# Overview.net
KiCad netlist of a schematic drawn in Altium Designer
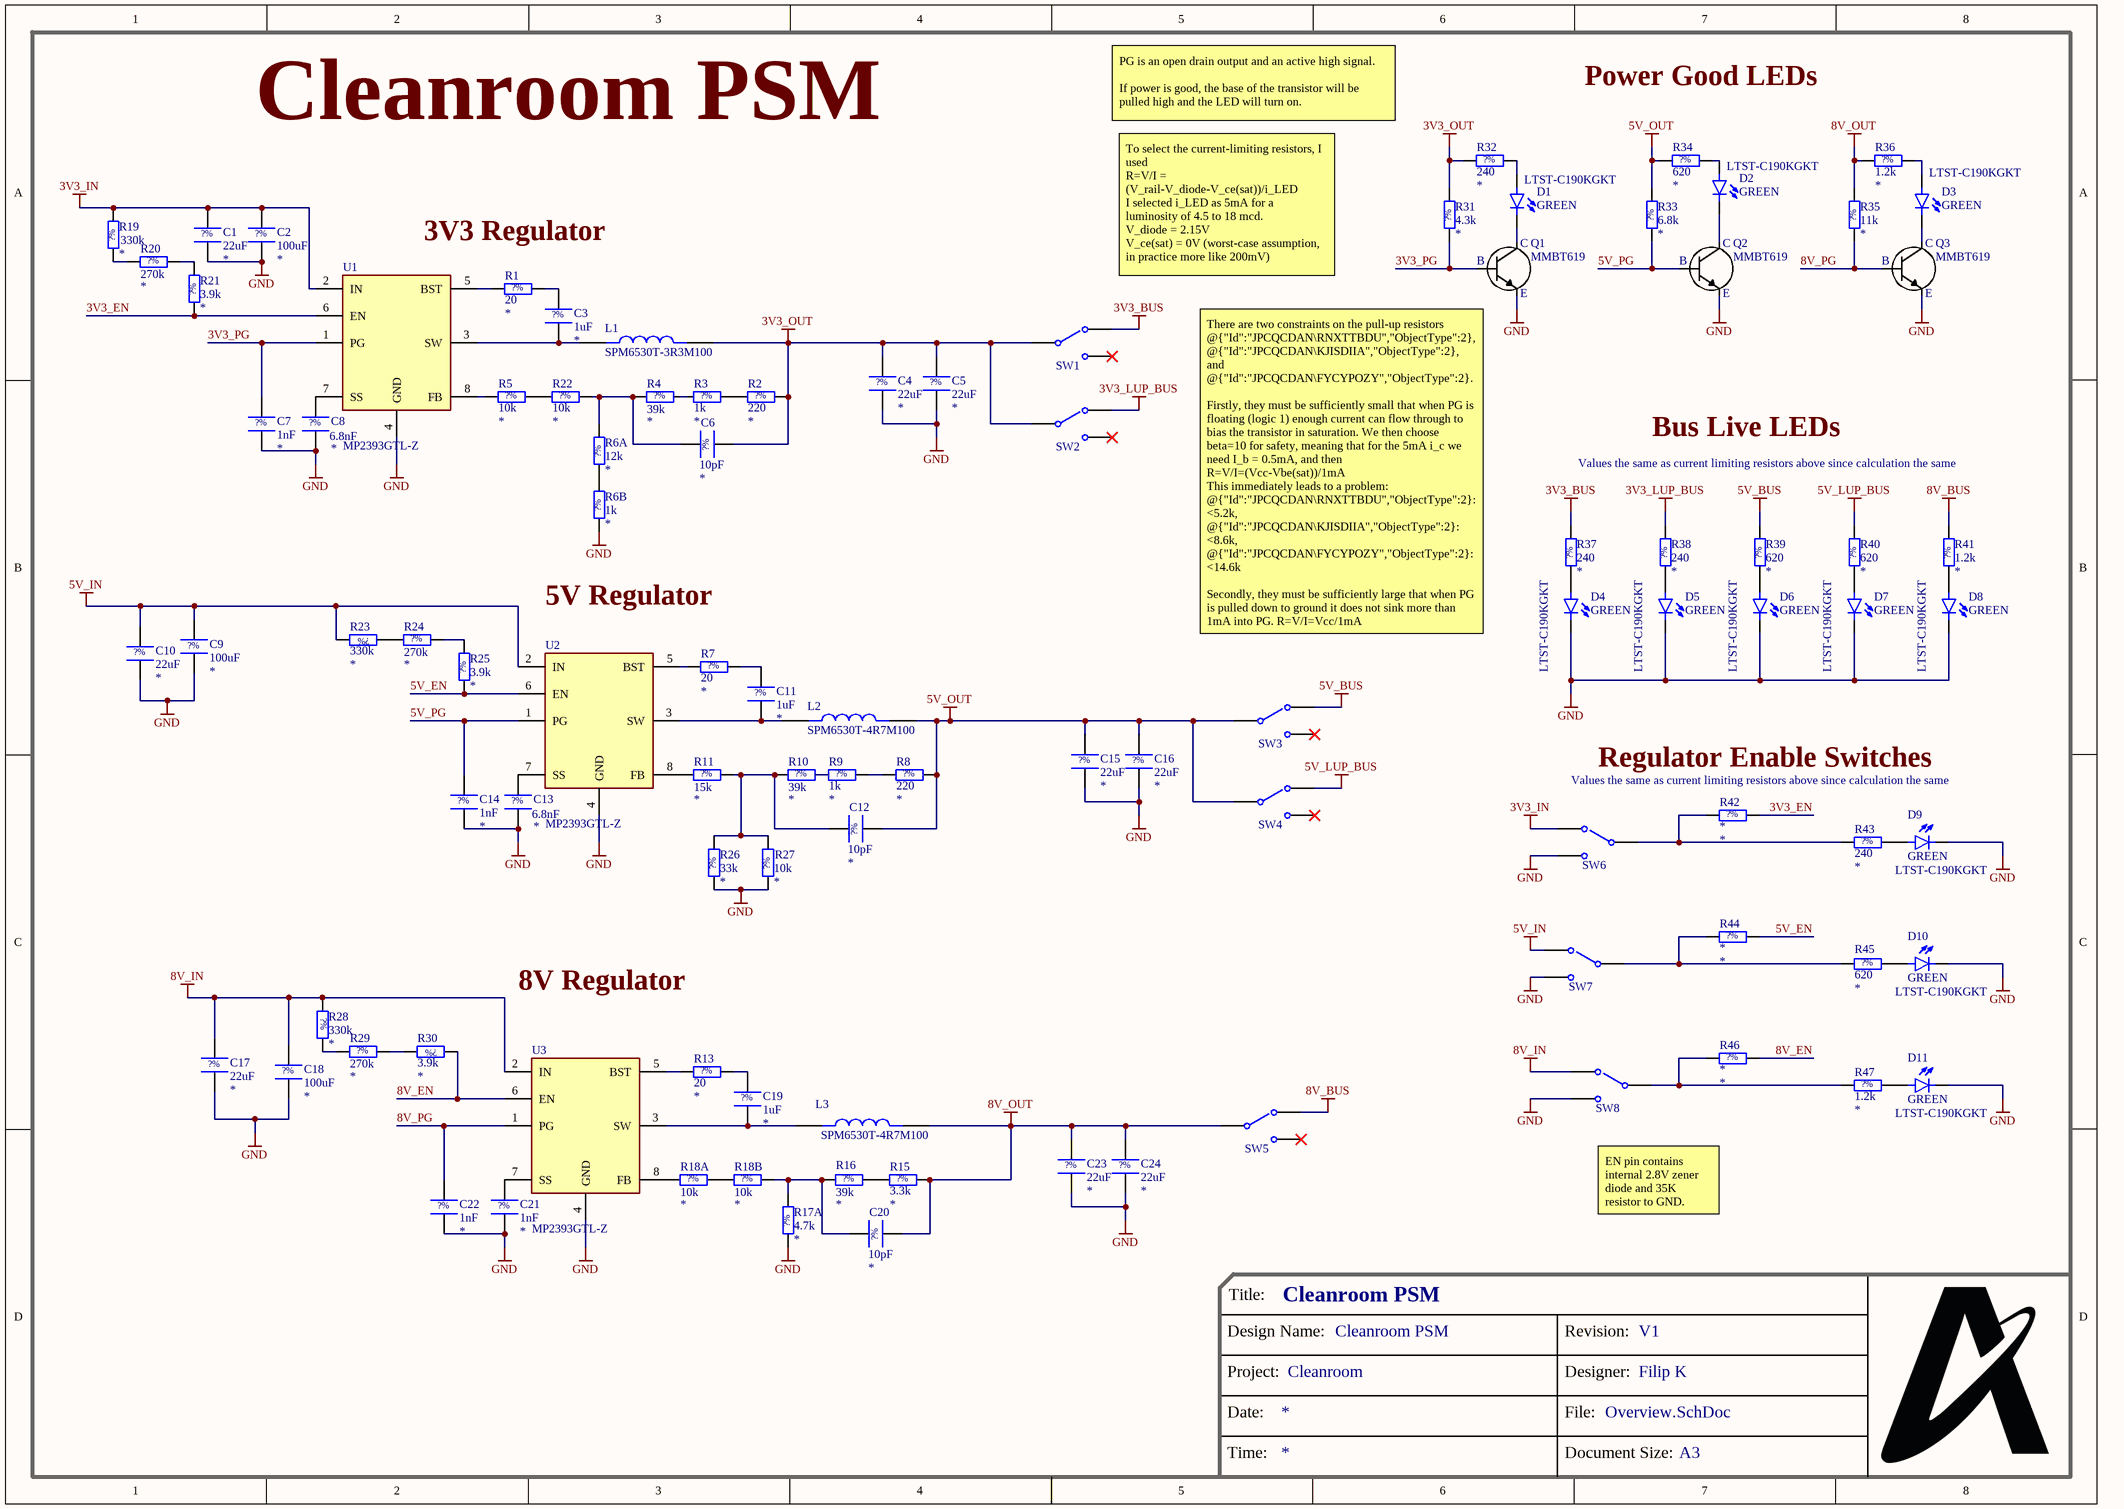
[diagram p0: Overview.SchDoc]

(export (version "E")
  (design (tool "Eeschema 10.0.6"))
  (components
    (comp (ref "C1")
      (value "22uF")
      (footprint "CAPACITOR_0805_2012M-70N")
      (description "Passive - Capacitor, Generic")
      (fields (field (name "TOLERANCE") "?%") (field (name "MF PART NO.") "*"))
      (libsource (lib "APSS Generic Components (3)") (part "Generic Capacitor"))
    )
    (comp (ref "C2")
      (value "100uF")
      (footprint "CAPACITOR_0805_2012M-70N")
      (description "Passive - Capacitor, Generic")
      (fields (field (name "TOLERANCE") "?%") (field (name "MF PART NO.") "*"))
      (libsource (lib "APSS Generic Components (3)") (part "Generic Capacitor"))
    )
    (comp (ref "C3")
      (value "1uF")
      (footprint "CAPACITOR_0805_2012M-70N")
      (description "Passive - Capacitor, Generic")
      (fields (field (name "TOLERANCE") "?%") (field (name "MF PART NO.") "*"))
      (libsource (lib "APSS Generic Components (3)") (part "Generic Capacitor"))
    )
    (comp (ref "C4")
      (value "22uF")
      (footprint "CAPACITOR_0805_2012M-70N")
      (description "Passive - Capacitor, Generic")
      (fields (field (name "TOLERANCE") "?%") (field (name "MF PART NO.") "*"))
      (libsource (lib "APSS Generic Components (3)") (part "Generic Capacitor"))
    )
    (comp (ref "C5")
      (value "22uF")
      (footprint "CAPACITOR_0805_2012M-70N")
      (description "Passive - Capacitor, Generic")
      (fields (field (name "TOLERANCE") "?%") (field (name "MF PART NO.") "*"))
      (libsource (lib "APSS Generic Components (3)") (part "Generic Capacitor"))
    )
    (comp (ref "C6")
      (value "10pF")
      (footprint "CAPACITOR_0805_2012M-70N")
      (description "Passive - Capacitor, Generic")
      (fields (field (name "TOLERANCE") "?%") (field (name "MF PART NO.") "*"))
      (libsource (lib "APSS Generic Components (3)") (part "Generic Capacitor"))
    )
    (comp (ref "C7")
      (value "1nF")
      (footprint "CAPACITOR_0805_2012M-70N")
      (description "Passive - Capacitor, Generic")
      (fields (field (name "TOLERANCE") "?%") (field (name "MF PART NO.") "*"))
      (libsource (lib "APSS Generic Components (3)") (part "Generic Capacitor"))
    )
    (comp (ref "C8")
      (value "6.8nF")
      (footprint "CAPACITOR_0805_2012M-70N")
      (description "Passive - Capacitor, Generic")
      (fields (field (name "TOLERANCE") "?%") (field (name "MF PART NO.") "*"))
      (libsource (lib "APSS Generic Components (3)") (part "Generic Capacitor"))
    )
    (comp (ref "C9")
      (value "100uF")
      (footprint "CAPACITOR_0805_2012M-70N")
      (description "Passive - Capacitor, Generic")
      (fields (field (name "TOLERANCE") "?%") (field (name "MF PART NO.") "*"))
      (libsource (lib "APSS Generic Components (3)") (part "Generic Capacitor"))
    )
    (comp (ref "C10")
      (value "22uF")
      (footprint "CAPACITOR_0805_2012M-70N")
      (description "Passive - Capacitor, Generic")
      (fields (field (name "TOLERANCE") "?%") (field (name "MF PART NO.") "*"))
      (libsource (lib "APSS Generic Components (3)") (part "Generic Capacitor"))
    )
    (comp (ref "C11")
      (value "1uF")
      (footprint "CAPACITOR_0805_2012M-70N")
      (description "Passive - Capacitor, Generic")
      (fields (field (name "TOLERANCE") "?%") (field (name "MF PART NO.") "*"))
      (libsource (lib "APSS Generic Components (3)") (part "Generic Capacitor"))
    )
    (comp (ref "C12")
      (value "10pF")
      (footprint "CAPACITOR_0805_2012M-70N")
      (description "Passive - Capacitor, Generic")
      (fields (field (name "TOLERANCE") "?%") (field (name "MF PART NO.") "*"))
      (libsource (lib "APSS Generic Components (3)") (part "Generic Capacitor"))
    )
    (comp (ref "C13")
      (value "6.8nF")
      (footprint "CAPACITOR_0805_2012M-70N")
      (description "Passive - Capacitor, Generic")
      (fields (field (name "TOLERANCE") "?%") (field (name "MF PART NO.") "*"))
      (libsource (lib "APSS Generic Components (3)") (part "Generic Capacitor"))
    )
    (comp (ref "C14")
      (value "1nF")
      (footprint "CAPACITOR_0805_2012M-70N")
      (description "Passive - Capacitor, Generic")
      (fields (field (name "TOLERANCE") "?%") (field (name "MF PART NO.") "*"))
      (libsource (lib "APSS Generic Components (3)") (part "Generic Capacitor"))
    )
    (comp (ref "C15")
      (value "22uF")
      (footprint "CAPACITOR_0805_2012M-70N")
      (description "Passive - Capacitor, Generic")
      (fields (field (name "TOLERANCE") "?%") (field (name "MF PART NO.") "*"))
      (libsource (lib "APSS Generic Components (3)") (part "Generic Capacitor"))
    )
    (comp (ref "C16")
      (value "22uF")
      (footprint "CAPACITOR_0805_2012M-70N")
      (description "Passive - Capacitor, Generic")
      (fields (field (name "TOLERANCE") "?%") (field (name "MF PART NO.") "*"))
      (libsource (lib "APSS Generic Components (3)") (part "Generic Capacitor"))
    )
    (comp (ref "C17")
      (value "22uF")
      (footprint "CAPACITOR_0805_2012M-70N")
      (description "Passive - Capacitor, Generic")
      (fields (field (name "TOLERANCE") "?%") (field (name "MF PART NO.") "*"))
      (libsource (lib "APSS Generic Components (3)") (part "Generic Capacitor"))
    )
    (comp (ref "C18")
      (value "100uF")
      (footprint "CAPACITOR_0805_2012M-70N")
      (description "Passive - Capacitor, Generic")
      (fields (field (name "TOLERANCE") "?%") (field (name "MF PART NO.") "*"))
      (libsource (lib "APSS Generic Components (3)") (part "Generic Capacitor"))
    )
    (comp (ref "C19")
      (value "1uF")
      (footprint "CAPACITOR_0805_2012M-70N")
      (description "Passive - Capacitor, Generic")
      (fields (field (name "TOLERANCE") "?%") (field (name "MF PART NO.") "*"))
      (libsource (lib "APSS Generic Components (3)") (part "Generic Capacitor"))
    )
    (comp (ref "C20")
      (value "10pF")
      (footprint "CAPACITOR_0805_2012M-70N")
      (description "Passive - Capacitor, Generic")
      (fields (field (name "TOLERANCE") "?%") (field (name "MF PART NO.") "*"))
      (libsource (lib "APSS Generic Components (3)") (part "Generic Capacitor"))
    )
    (comp (ref "C21")
      (value "1nF")
      (footprint "CAPACITOR_0805_2012M-70N")
      (description "Passive - Capacitor, Generic")
      (fields (field (name "TOLERANCE") "?%") (field (name "MF PART NO.") "*"))
      (libsource (lib "APSS Generic Components (3)") (part "Generic Capacitor"))
    )
    (comp (ref "C22")
      (value "1nF")
      (footprint "CAPACITOR_0805_2012M-70N")
      (description "Passive - Capacitor, Generic")
      (fields (field (name "TOLERANCE") "?%") (field (name "MF PART NO.") "*"))
      (libsource (lib "APSS Generic Components (3)") (part "Generic Capacitor"))
    )
    (comp (ref "C23")
      (value "22uF")
      (footprint "CAPACITOR_0805_2012M-70N")
      (description "Passive - Capacitor, Generic")
      (fields (field (name "TOLERANCE") "?%") (field (name "MF PART NO.") "*"))
      (libsource (lib "APSS Generic Components (3)") (part "Generic Capacitor"))
    )
    (comp (ref "C24")
      (value "22uF")
      (footprint "CAPACITOR_0805_2012M-70N")
      (description "Passive - Capacitor, Generic")
      (fields (field (name "TOLERANCE") "?%") (field (name "MF PART NO.") "*"))
      (libsource (lib "APSS Generic Components (3)") (part "Generic Capacitor"))
    )
    (comp (ref "D1")
      (value "LTST-C190 Series")
      (footprint "APSS Prototype Parts:LED_0603_1608M_0.80mm")
      (description "Diode - LED, 0603")
      (fields
        (field (name "APSS STANDARD PART") "APSS Standard")
        (field (name "MF PART NO.") "LTST-C190KGKT")
        (field (name "COLOUR") "GREEN")
      )
      (libsource (lib "APSS Prototype Parts") (part "LTST-C190 Series"))
    )
    (comp (ref "D2")
      (value "LTST-C190 Series")
      (footprint "APSS Prototype Parts:LED_0603_1608M_0.80mm")
      (description "Diode - LED, 0603")
      (fields
        (field (name "APSS STANDARD PART") "APSS Standard")
        (field (name "MF PART NO.") "LTST-C190KGKT")
        (field (name "COLOUR") "GREEN")
      )
      (libsource (lib "APSS Prototype Parts") (part "LTST-C190 Series"))
    )
    (comp (ref "D3")
      (value "LTST-C190 Series")
      (footprint "APSS Prototype Parts:LED_0603_1608M_0.80mm")
      (description "Diode - LED, 0603")
      (fields
        (field (name "APSS STANDARD PART") "APSS Standard")
        (field (name "MF PART NO.") "LTST-C190KGKT")
        (field (name "COLOUR") "GREEN")
      )
      (libsource (lib "APSS Prototype Parts") (part "LTST-C190 Series"))
    )
    (comp (ref "D4")
      (value "LTST-C190 Series")
      (footprint "APSS Prototype Parts:LED_0603_1608M_0.80mm")
      (description "Diode - LED, 0603")
      (fields
        (field (name "APSS STANDARD PART") "APSS Standard")
        (field (name "MF PART NO.") "LTST-C190KGKT")
        (field (name "COLOUR") "GREEN")
      )
      (libsource (lib "APSS Prototype Parts") (part "LTST-C190 Series"))
    )
    (comp (ref "D5")
      (value "LTST-C190 Series")
      (footprint "APSS Prototype Parts:LED_0603_1608M_0.80mm")
      (description "Diode - LED, 0603")
      (fields
        (field (name "APSS STANDARD PART") "APSS Standard")
        (field (name "MF PART NO.") "LTST-C190KGKT")
        (field (name "COLOUR") "GREEN")
      )
      (libsource (lib "APSS Prototype Parts") (part "LTST-C190 Series"))
    )
    (comp (ref "D6")
      (value "LTST-C190 Series")
      (footprint "APSS Prototype Parts:LED_0603_1608M_0.80mm")
      (description "Diode - LED, 0603")
      (fields
        (field (name "APSS STANDARD PART") "APSS Standard")
        (field (name "MF PART NO.") "LTST-C190KGKT")
        (field (name "COLOUR") "GREEN")
      )
      (libsource (lib "APSS Prototype Parts") (part "LTST-C190 Series"))
    )
    (comp (ref "D7")
      (value "LTST-C190 Series")
      (footprint "APSS Prototype Parts:LED_0603_1608M_0.80mm")
      (description "Diode - LED, 0603")
      (fields
        (field (name "APSS STANDARD PART") "APSS Standard")
        (field (name "MF PART NO.") "LTST-C190KGKT")
        (field (name "COLOUR") "GREEN")
      )
      (libsource (lib "APSS Prototype Parts") (part "LTST-C190 Series"))
    )
    (comp (ref "D8")
      (value "LTST-C190 Series")
      (footprint "APSS Prototype Parts:LED_0603_1608M_0.80mm")
      (description "Diode - LED, 0603")
      (fields
        (field (name "APSS STANDARD PART") "APSS Standard")
        (field (name "MF PART NO.") "LTST-C190KGKT")
        (field (name "COLOUR") "GREEN")
      )
      (libsource (lib "APSS Prototype Parts") (part "LTST-C190 Series"))
    )
    (comp (ref "D9")
      (value "LTST-C190 Series")
      (footprint "APSS Prototype Parts:LED_0603_1608M_0.80mm")
      (description "Diode - LED, 0603")
      (fields
        (field (name "APSS STANDARD PART") "APSS Standard")
        (field (name "MF PART NO.") "LTST-C190KGKT")
        (field (name "COLOUR") "GREEN")
      )
      (libsource (lib "APSS Prototype Parts") (part "LTST-C190 Series"))
    )
    (comp (ref "D10")
      (value "LTST-C190 Series")
      (footprint "APSS Prototype Parts:LED_0603_1608M_0.80mm")
      (description "Diode - LED, 0603")
      (fields
        (field (name "APSS STANDARD PART") "APSS Standard")
        (field (name "MF PART NO.") "LTST-C190KGKT")
        (field (name "COLOUR") "GREEN")
      )
      (libsource (lib "APSS Prototype Parts") (part "LTST-C190 Series"))
    )
    (comp (ref "D11")
      (value "LTST-C190 Series")
      (footprint "APSS Prototype Parts:LED_0603_1608M_0.80mm")
      (description "Diode - LED, 0603")
      (fields
        (field (name "APSS STANDARD PART") "APSS Standard")
        (field (name "MF PART NO.") "LTST-C190KGKT")
        (field (name "COLOUR") "GREEN")
      )
      (libsource (lib "APSS Prototype Parts") (part "LTST-C190 Series"))
    )
    (comp (ref "L1")
      (value "SPM6530T-3R3M100")
      (footprint "IND_SPM6530T-1R5M100")
      (description "1.5 ÂµH Shielded Drum Core, Wirewound Inductor 11 A 10.67mOhm Max Nonstandard")
      (fields (field (name "DIGI-KEY_PART_NUMBER") "445-3881-2-ND") (field (name "MF") "TDK"))
      (libsource (lib "SPM6530T-1R5M100") (part "SPM6530T-1R5M100"))
    )
    (comp (ref "L2")
      (value "SPM6530T-4R7M100")
      (footprint "IND_SPM6530T-1R5M100")
      (description "1.5 ÂµH Shielded Drum Core, Wirewound Inductor 11 A 10.67mOhm Max Nonstandard")
      (fields (field (name "DIGI-KEY_PART_NUMBER") "445-3881-2-ND") (field (name "MF") "TDK"))
      (libsource (lib "SPM6530T-1R5M100") (part "SPM6530T-1R5M100"))
    )
    (comp (ref "L3")
      (value "SPM6530T-4R7M100")
      (footprint "IND_SPM6530T-1R5M100")
      (description "1.5 ÂµH Shielded Drum Core, Wirewound Inductor 11 A 10.67mOhm Max Nonstandard")
      (fields (field (name "DIGI-KEY_PART_NUMBER") "445-3881-2-ND") (field (name "MF") "TDK"))
      (libsource (lib "SPM6530T-1R5M100") (part "SPM6530T-1R5M100"))
    )
    (comp (ref "Q1")
      (value "MMBT619")
      (footprint "APSS Prototype Parts:SOT23-3N-1.15mm")
      (description "Transistor - BJT NPN MMBT619")
      (fields (field (name "POWER") "350mW") (field (name "APSS STANDARD PART") "APSS Standard"))
      (libsource (lib "APSS Prototype Parts") (part "MMBT619"))
    )
    (comp (ref "Q2")
      (value "MMBT619")
      (footprint "APSS Prototype Parts:SOT23-3N-1.15mm")
      (description "Transistor - BJT NPN MMBT619")
      (fields (field (name "POWER") "350mW") (field (name "APSS STANDARD PART") "APSS Standard"))
      (libsource (lib "APSS Prototype Parts") (part "MMBT619"))
    )
    (comp (ref "Q3")
      (value "MMBT619")
      (footprint "APSS Prototype Parts:SOT23-3N-1.15mm")
      (description "Transistor - BJT NPN MMBT619")
      (fields (field (name "POWER") "350mW") (field (name "APSS STANDARD PART") "APSS Standard"))
      (libsource (lib "APSS Prototype Parts") (part "MMBT619"))
    )
    (comp (ref "R1")
      (value "20")
      (footprint "RESISTOR_0805_2012M-50N")
      (description "Passive - Resistor, Generic")
      (fields (field (name "TOLERANCE") "?%") (field (name "MF PART NO.") "*"))
      (libsource (lib "APSS Generic Components (3)") (part "Generic Resistor"))
    )
    (comp (ref "R2")
      (value "220")
      (footprint "RESISTOR_0805_2012M-50N")
      (description "Passive - Resistor, Generic")
      (fields (field (name "TOLERANCE") "?%") (field (name "MF PART NO.") "*"))
      (libsource (lib "APSS Generic Components (3)") (part "Generic Resistor"))
    )
    (comp (ref "R3")
      (value "1k")
      (footprint "RESISTOR_0805_2012M-50N")
      (description "Passive - Resistor, Generic")
      (fields (field (name "TOLERANCE") "?%") (field (name "MF PART NO.") "*"))
      (libsource (lib "APSS Generic Components (3)") (part "Generic Resistor"))
    )
    (comp (ref "R4")
      (value "39k")
      (footprint "RESISTOR_0805_2012M-50N")
      (description "Passive - Resistor, Generic")
      (fields (field (name "TOLERANCE") "?%") (field (name "MF PART NO.") "*"))
      (libsource (lib "APSS Generic Components (3)") (part "Generic Resistor"))
    )
    (comp (ref "R5")
      (value "10k")
      (footprint "RESISTOR_0805_2012M-50N")
      (description "Passive - Resistor, Generic")
      (fields (field (name "TOLERANCE") "?%") (field (name "MF PART NO.") "*"))
      (libsource (lib "APSS Generic Components (3)") (part "Generic Resistor"))
    )
    (comp (ref "R6A")
      (value "12k")
      (footprint "RESISTOR_0805_2012M-50N")
      (description "Passive - Resistor, Generic")
      (fields (field (name "TOLERANCE") "?%") (field (name "MF PART NO.") "*"))
      (libsource (lib "") (part "Generic Resistor_1"))
    )
    (comp (ref "R6B")
      (value "1k")
      (footprint "RESISTOR_0805_2012M-50N")
      (description "Passive - Resistor, Generic")
      (fields (field (name "TOLERANCE") "?%") (field (name "MF PART NO.") "*"))
      (libsource (lib "") (part "Generic Resistor_1"))
    )
    (comp (ref "R7")
      (value "20")
      (footprint "RESISTOR_0805_2012M-50N")
      (description "Passive - Resistor, Generic")
      (fields (field (name "TOLERANCE") "?%") (field (name "MF PART NO.") "*"))
      (libsource (lib "APSS Generic Components (3)") (part "Generic Resistor"))
    )
    (comp (ref "R8")
      (value "220")
      (footprint "RESISTOR_0805_2012M-50N")
      (description "Passive - Resistor, Generic")
      (fields (field (name "TOLERANCE") "?%") (field (name "MF PART NO.") "*"))
      (libsource (lib "APSS Generic Components (3)") (part "Generic Resistor"))
    )
    (comp (ref "R9")
      (value "1k")
      (footprint "RESISTOR_0805_2012M-50N")
      (description "Passive - Resistor, Generic")
      (fields (field (name "TOLERANCE") "?%") (field (name "MF PART NO.") "*"))
      (libsource (lib "APSS Generic Components (3)") (part "Generic Resistor"))
    )
    (comp (ref "R10")
      (value "39k")
      (footprint "RESISTOR_0805_2012M-50N")
      (description "Passive - Resistor, Generic")
      (fields (field (name "TOLERANCE") "?%") (field (name "MF PART NO.") "*"))
      (libsource (lib "APSS Generic Components (3)") (part "Generic Resistor"))
    )
    (comp (ref "R11")
      (value "15k")
      (footprint "RESISTOR_0805_2012M-50N")
      (description "Passive - Resistor, Generic")
      (fields (field (name "TOLERANCE") "?%") (field (name "MF PART NO.") "*"))
      (libsource (lib "APSS Generic Components (3)") (part "Generic Resistor"))
    )
    (comp (ref "R13")
      (value "20")
      (footprint "RESISTOR_0805_2012M-50N")
      (description "Passive - Resistor, Generic")
      (fields (field (name "TOLERANCE") "?%") (field (name "MF PART NO.") "*"))
      (libsource (lib "APSS Generic Components (3)") (part "Generic Resistor"))
    )
    (comp (ref "R15")
      (value "3.3k")
      (footprint "RESISTOR_0805_2012M-50N")
      (description "Passive - Resistor, Generic")
      (fields (field (name "TOLERANCE") "?%") (field (name "MF PART NO.") "*"))
      (libsource (lib "APSS Generic Components (3)") (part "Generic Resistor"))
    )
    (comp (ref "R16")
      (value "39k")
      (footprint "RESISTOR_0805_2012M-50N")
      (description "Passive - Resistor, Generic")
      (fields (field (name "TOLERANCE") "?%") (field (name "MF PART NO.") "*"))
      (libsource (lib "APSS Generic Components (3)") (part "Generic Resistor"))
    )
    (comp (ref "R17A")
      (value "4.7k")
      (footprint "RESISTOR_0805_2012M-50N")
      (description "Passive - Resistor, Generic")
      (fields (field (name "TOLERANCE") "?%") (field (name "MF PART NO.") "*"))
      (libsource (lib "") (part "Generic Resistor_1"))
    )
    (comp (ref "R18A")
      (value "10k")
      (footprint "RESISTOR_0805_2012M-50N")
      (description "Passive - Resistor, Generic")
      (fields (field (name "TOLERANCE") "?%") (field (name "MF PART NO.") "*"))
      (libsource (lib "APSS Generic Components (3)") (part "Generic Resistor"))
    )
    (comp (ref "R18B")
      (value "10k")
      (footprint "RESISTOR_0805_2012M-50N")
      (description "Passive - Resistor, Generic")
      (fields (field (name "TOLERANCE") "?%") (field (name "MF PART NO.") "*"))
      (libsource (lib "APSS Generic Components (3)") (part "Generic Resistor"))
    )
    (comp (ref "R19")
      (value "330k")
      (footprint "RESISTOR_0805_2012M-50N")
      (description "Passive - Resistor, Generic")
      (fields (field (name "TOLERANCE") "?%") (field (name "MF PART NO.") "*"))
      (libsource (lib "") (part "Generic Resistor_1"))
    )
    (comp (ref "R20")
      (value "270k")
      (footprint "RESISTOR_0805_2012M-50N")
      (description "Passive - Resistor, Generic")
      (fields (field (name "TOLERANCE") "?%") (field (name "MF PART NO.") "*"))
      (libsource (lib "APSS Generic Components (3)") (part "Generic Resistor"))
    )
    (comp (ref "R21")
      (value "3.9k")
      (footprint "RESISTOR_0805_2012M-50N")
      (description "Passive - Resistor, Generic")
      (fields (field (name "TOLERANCE") "?%") (field (name "MF PART NO.") "*"))
      (libsource (lib "") (part "Generic Resistor_1"))
    )
    (comp (ref "R22")
      (value "10k")
      (footprint "RESISTOR_0805_2012M-50N")
      (description "Passive - Resistor, Generic")
      (fields (field (name "TOLERANCE") "?%") (field (name "MF PART NO.") "*"))
      (libsource (lib "APSS Generic Components (3)") (part "Generic Resistor"))
    )
    (comp (ref "R23")
      (value "330k")
      (footprint "RESISTOR_0805_2012M-50N")
      (description "Passive - Resistor, Generic")
      (fields (field (name "TOLERANCE") "?%") (field (name "MF PART NO.") "*"))
      (libsource (lib "") (part "Generic Resistor_2"))
    )
    (comp (ref "R24")
      (value "270k")
      (footprint "RESISTOR_0805_2012M-50N")
      (description "Passive - Resistor, Generic")
      (fields (field (name "TOLERANCE") "?%") (field (name "MF PART NO.") "*"))
      (libsource (lib "APSS Generic Components (3)") (part "Generic Resistor"))
    )
    (comp (ref "R25")
      (value "3.9k")
      (footprint "RESISTOR_0805_2012M-50N")
      (description "Passive - Resistor, Generic")
      (fields (field (name "TOLERANCE") "?%") (field (name "MF PART NO.") "*"))
      (libsource (lib "") (part "Generic Resistor_1"))
    )
    (comp (ref "R26")
      (value "33k")
      (footprint "RESISTOR_0805_2012M-50N")
      (description "Passive - Resistor, Generic")
      (fields (field (name "TOLERANCE") "?%") (field (name "MF PART NO.") "*"))
      (libsource (lib "") (part "Generic Resistor_1"))
    )
    (comp (ref "R27")
      (value "10k")
      (footprint "RESISTOR_0805_2012M-50N")
      (description "Passive - Resistor, Generic")
      (fields (field (name "TOLERANCE") "?%") (field (name "MF PART NO.") "*"))
      (libsource (lib "") (part "Generic Resistor_1"))
    )
    (comp (ref "R28")
      (value "330k")
      (footprint "RESISTOR_0805_2012M-50N")
      (description "Passive - Resistor, Generic")
      (fields (field (name "TOLERANCE") "?%") (field (name "MF PART NO.") "*"))
      (libsource (lib "") (part "Generic Resistor_3"))
    )
    (comp (ref "R29")
      (value "270k")
      (footprint "RESISTOR_0805_2012M-50N")
      (description "Passive - Resistor, Generic")
      (fields (field (name "TOLERANCE") "?%") (field (name "MF PART NO.") "*"))
      (libsource (lib "APSS Generic Components (3)") (part "Generic Resistor"))
    )
    (comp (ref "R30")
      (value "3.9k")
      (footprint "RESISTOR_0805_2012M-50N")
      (description "Passive - Resistor, Generic")
      (fields (field (name "TOLERANCE") "?%") (field (name "MF PART NO.") "*"))
      (libsource (lib "") (part "Generic Resistor_2"))
    )
    (comp (ref "R31")
      (value "4.3k")
      (footprint "RESISTOR_0805_2012M-50N")
      (description "Passive - Resistor, Generic")
      (fields (field (name "TOLERANCE") "?%") (field (name "MF PART NO.") "*"))
      (libsource (lib "") (part "Generic Resistor_1"))
    )
    (comp (ref "R32")
      (value "240")
      (footprint "RESISTOR_0805_2012M-50N")
      (description "Passive - Resistor, Generic")
      (fields (field (name "TOLERANCE") "?%") (field (name "MF PART NO.") "*"))
      (libsource (lib "APSS Generic Components (3)") (part "Generic Resistor"))
    )
    (comp (ref "R33")
      (value "6.8k")
      (footprint "RESISTOR_0805_2012M-50N")
      (description "Passive - Resistor, Generic")
      (fields (field (name "TOLERANCE") "?%") (field (name "MF PART NO.") "*"))
      (libsource (lib "") (part "Generic Resistor_1"))
    )
    (comp (ref "R34")
      (value "620")
      (footprint "RESISTOR_0805_2012M-50N")
      (description "Passive - Resistor, Generic")
      (fields (field (name "TOLERANCE") "?%") (field (name "MF PART NO.") "*"))
      (libsource (lib "APSS Generic Components (3)") (part "Generic Resistor"))
    )
    (comp (ref "R35")
      (value "11k")
      (footprint "RESISTOR_0805_2012M-50N")
      (description "Passive - Resistor, Generic")
      (fields (field (name "TOLERANCE") "?%") (field (name "MF PART NO.") "*"))
      (libsource (lib "") (part "Generic Resistor_1"))
    )
    (comp (ref "R36")
      (value "1.2k")
      (footprint "RESISTOR_0805_2012M-50N")
      (description "Passive - Resistor, Generic")
      (fields (field (name "TOLERANCE") "?%") (field (name "MF PART NO.") "*"))
      (libsource (lib "APSS Generic Components (3)") (part "Generic Resistor"))
    )
    (comp (ref "R37")
      (value "240")
      (footprint "RESISTOR_0805_2012M-50N")
      (description "Passive - Resistor, Generic")
      (fields (field (name "TOLERANCE") "?%") (field (name "MF PART NO.") "*"))
      (libsource (lib "") (part "Generic Resistor_1"))
    )
    (comp (ref "R38")
      (value "240")
      (footprint "RESISTOR_0805_2012M-50N")
      (description "Passive - Resistor, Generic")
      (fields (field (name "TOLERANCE") "?%") (field (name "MF PART NO.") "*"))
      (libsource (lib "") (part "Generic Resistor_1"))
    )
    (comp (ref "R39")
      (value "620")
      (footprint "RESISTOR_0805_2012M-50N")
      (description "Passive - Resistor, Generic")
      (fields (field (name "TOLERANCE") "?%") (field (name "MF PART NO.") "*"))
      (libsource (lib "") (part "Generic Resistor_1"))
    )
    (comp (ref "R40")
      (value "620")
      (footprint "RESISTOR_0805_2012M-50N")
      (description "Passive - Resistor, Generic")
      (fields (field (name "TOLERANCE") "?%") (field (name "MF PART NO.") "*"))
      (libsource (lib "") (part "Generic Resistor_1"))
    )
    (comp (ref "R41")
      (value "1.2k")
      (footprint "RESISTOR_0805_2012M-50N")
      (description "Passive - Resistor, Generic")
      (fields (field (name "TOLERANCE") "?%") (field (name "MF PART NO.") "*"))
      (libsource (lib "") (part "Generic Resistor_1"))
    )
    (comp (ref "R42")
      (value "*")
      (footprint "RESISTOR_0805_2012M-50N")
      (description "Passive - Resistor, Generic")
      (fields
        (field (name "TOLERANCE") "?%")
        (field (name "MF PART NO.") "*")
        (field (name "ALTIUM_VALUE") "*")
      )
      (libsource (lib "APSS Generic Components (3)") (part "Generic Resistor"))
    )
    (comp (ref "R43")
      (value "240")
      (footprint "RESISTOR_0805_2012M-50N")
      (description "Passive - Resistor, Generic")
      (fields (field (name "TOLERANCE") "?%") (field (name "MF PART NO.") "*"))
      (libsource (lib "APSS Generic Components (3)") (part "Generic Resistor"))
    )
    (comp (ref "R44")
      (value "*")
      (footprint "RESISTOR_0805_2012M-50N")
      (description "Passive - Resistor, Generic")
      (fields
        (field (name "TOLERANCE") "?%")
        (field (name "MF PART NO.") "*")
        (field (name "ALTIUM_VALUE") "*")
      )
      (libsource (lib "APSS Generic Components (3)") (part "Generic Resistor"))
    )
    (comp (ref "R45")
      (value "620")
      (footprint "RESISTOR_0805_2012M-50N")
      (description "Passive - Resistor, Generic")
      (fields (field (name "TOLERANCE") "?%") (field (name "MF PART NO.") "*"))
      (libsource (lib "APSS Generic Components (3)") (part "Generic Resistor"))
    )
    (comp (ref "R46")
      (value "*")
      (footprint "RESISTOR_0805_2012M-50N")
      (description "Passive - Resistor, Generic")
      (fields
        (field (name "TOLERANCE") "?%")
        (field (name "MF PART NO.") "*")
        (field (name "ALTIUM_VALUE") "*")
      )
      (libsource (lib "APSS Generic Components (3)") (part "Generic Resistor"))
    )
    (comp (ref "R47")
      (value "1.2k")
      (footprint "RESISTOR_0805_2012M-50N")
      (description "Passive - Resistor, Generic")
      (fields (field (name "TOLERANCE") "?%") (field (name "MF PART NO.") "*"))
      (libsource (lib "APSS Generic Components (3)") (part "Generic Resistor"))
    )
    (comp (ref "SW1")
      (value "ANT11SF1CQE")
      (footprint "ANT11SF1CQE")
      (description "Switch - Toggle, SPDT, 5A @ 28VDC")
      (libsource (lib "ANT11SF1CQE") (part "ANT11SF1CQE"))
    )
    (comp (ref "SW2")
      (value "ANT11SF1CQE")
      (footprint "ANT11SF1CQE")
      (description "Switch - Toggle, SPDT, 5A @ 28VDC")
      (libsource (lib "ANT11SF1CQE") (part "ANT11SF1CQE"))
    )
    (comp (ref "SW3")
      (value "ANT11SF1CQE")
      (footprint "ANT11SF1CQE")
      (description "Switch - Toggle, SPDT, 5A @ 28VDC")
      (libsource (lib "ANT11SF1CQE") (part "ANT11SF1CQE"))
    )
    (comp (ref "SW4")
      (value "ANT11SF1CQE")
      (footprint "ANT11SF1CQE")
      (description "Switch - Toggle, SPDT, 5A @ 28VDC")
      (libsource (lib "ANT11SF1CQE") (part "ANT11SF1CQE"))
    )
    (comp (ref "SW5")
      (value "ANT11SF1CQE")
      (footprint "ANT11SF1CQE")
      (description "Switch - Toggle, SPDT, 5A @ 28VDC")
      (libsource (lib "ANT11SF1CQE") (part "ANT11SF1CQE"))
    )
    (comp (ref "SW6")
      (value "ANT11SF1CQE")
      (footprint "ANT11SF1CQE")
      (description "Switch - Toggle, SPDT, 5A @ 28VDC")
      (libsource (lib "ANT11SF1CQE") (part "ANT11SF1CQE"))
    )
    (comp (ref "SW7")
      (value "ANT11SF1CQE")
      (footprint "ANT11SF1CQE")
      (description "Switch - Toggle, SPDT, 5A @ 28VDC")
      (libsource (lib "ANT11SF1CQE") (part "ANT11SF1CQE"))
    )
    (comp (ref "SW8")
      (value "ANT11SF1CQE")
      (footprint "ANT11SF1CQE")
      (description "Switch - Toggle, SPDT, 5A @ 28VDC")
      (libsource (lib "ANT11SF1CQE") (part "ANT11SF1CQE"))
    )
    (comp (ref "U1")
      (value "MP2393GTL-Z")
      (footprint "SOT-583-2.1mmx1.6mmBody-0.6mm")
      (description "IC - Regulator, Switching, 3A, 4.2V to 24V In, 0.8V to 13V Out, SOT-583")
      (libsource (lib "MP2393GTL-Z") (part "MP2393GTL-Z"))
    )
    (comp (ref "U2")
      (value "MP2393GTL-Z")
      (footprint "SOT-583-2.1mmx1.6mmBody-0.6mm")
      (description "IC - Regulator, Switching, 3A, 4.2V to 24V In, 0.8V to 13V Out, SOT-583")
      (libsource (lib "MP2393GTL-Z") (part "MP2393GTL-Z"))
    )
    (comp (ref "U3")
      (value "MP2393GTL-Z")
      (footprint "SOT-583-2.1mmx1.6mmBody-0.6mm")
      (description "IC - Regulator, Switching, 3A, 4.2V to 24V In, 0.8V to 13V Out, SOT-583")
      (libsource (lib "MP2393GTL-Z") (part "MP2393GTL-Z"))
    )
  )
  (nets
    (net (code "1") (name "/3V3_EN") (class "Default")
      (node (ref "R21") (pin "1") (pinfunction "1_1") (pintype "passive"))
      (node (ref "R42") (pin "2") (pinfunction "2_2") (pintype "passive"))
      (node (ref "U1") (pin "6") (pinfunction "EN_6") (pintype "passive"))
    )
    (net (code "2") (name "/3V3_PG") (class "Default")
      (node (ref "C7") (pin "2") (pinfunction "2_2") (pintype "passive"))
      (node (ref "Q1") (pin "1") (pinfunction "B_1") (pintype "passive"))
      (node (ref "R31") (pin "1") (pinfunction "1_1") (pintype "passive"))
      (node (ref "U1") (pin "1") (pinfunction "PG_1") (pintype "power_in"))
    )
    (net (code "3") (name "/5V_EN") (class "Default")
      (node (ref "R25") (pin "1") (pinfunction "1_1") (pintype "passive"))
      (node (ref "R44") (pin "2") (pinfunction "2_2") (pintype "passive"))
      (node (ref "U2") (pin "6") (pinfunction "EN_6") (pintype "passive"))
    )
    (net (code "4") (name "/5V_PG") (class "Default")
      (node (ref "C14") (pin "2") (pinfunction "2_2") (pintype "passive"))
      (node (ref "Q2") (pin "1") (pinfunction "B_1") (pintype "passive"))
      (node (ref "R33") (pin "1") (pinfunction "1_1") (pintype "passive"))
      (node (ref "U2") (pin "1") (pinfunction "PG_1") (pintype "power_in"))
    )
    (net (code "5") (name "/8V_EN") (class "Default")
      (node (ref "R30") (pin "1") (pinfunction "1_1") (pintype "passive"))
      (node (ref "R46") (pin "2") (pinfunction "2_2") (pintype "passive"))
      (node (ref "U3") (pin "6") (pinfunction "EN_6") (pintype "passive"))
    )
    (net (code "6") (name "/8V_PG") (class "Default")
      (node (ref "C22") (pin "2") (pinfunction "2_2") (pintype "passive"))
      (node (ref "Q3") (pin "1") (pinfunction "B_1") (pintype "passive"))
      (node (ref "R35") (pin "1") (pinfunction "1_1") (pintype "passive"))
      (node (ref "U3") (pin "1") (pinfunction "PG_1") (pintype "power_in"))
    )
    (net (code "7") (name "3V3_BUS") (class "Default")
      (node (ref "R37") (pin "2") (pinfunction "2_2") (pintype "passive"))
      (node (ref "SW1") (pin "1") (pinfunction "1_1") (pintype "power_in"))
    )
    (net (code "8") (name "3V3_IN") (class "Default")
      (node (ref "C1") (pin "2") (pinfunction "2_2") (pintype "passive"))
      (node (ref "C2") (pin "2") (pinfunction "2_2") (pintype "passive"))
      (node (ref "R19") (pin "2") (pinfunction "2_2") (pintype "passive"))
      (node (ref "SW6") (pin "1") (pinfunction "1_1") (pintype "power_in"))
      (node (ref "U1") (pin "2") (pinfunction "IN_2") (pintype "power_in"))
    )
    (net (code "9") (name "3V3_LUP_BUS") (class "Default")
      (node (ref "R38") (pin "2") (pinfunction "2_2") (pintype "passive"))
      (node (ref "SW2") (pin "1") (pinfunction "1_1") (pintype "power_in"))
    )
    (net (code "10") (name "3V3_OUT") (class "Default")
      (node (ref "C4") (pin "2") (pinfunction "2_2") (pintype "passive"))
      (node (ref "C5") (pin "2") (pinfunction "2_2") (pintype "passive"))
      (node (ref "C6") (pin "1") (pinfunction "1_1") (pintype "passive"))
      (node (ref "L1") (pin "2") (pinfunction "2_2") (pintype "passive"))
      (node (ref "R2") (pin "2") (pinfunction "2_2") (pintype "passive"))
      (node (ref "R31") (pin "2") (pinfunction "2_2") (pintype "passive"))
      (node (ref "R32") (pin "1") (pinfunction "1_1") (pintype "passive"))
      (node (ref "SW1") (pin "2") (pinfunction "2_2") (pintype "power_in"))
      (node (ref "SW2") (pin "2") (pinfunction "2_2") (pintype "power_in"))
    )
    (net (code "11") (name "5V_BUS") (class "Default")
      (node (ref "R39") (pin "2") (pinfunction "2_2") (pintype "passive"))
      (node (ref "SW3") (pin "1") (pinfunction "1_1") (pintype "power_in"))
    )
    (net (code "12") (name "5V_IN") (class "Default")
      (node (ref "C10") (pin "2") (pinfunction "2_2") (pintype "passive"))
      (node (ref "C9") (pin "2") (pinfunction "2_2") (pintype "passive"))
      (node (ref "R23") (pin "2") (pinfunction "2_2") (pintype "passive"))
      (node (ref "SW7") (pin "1") (pinfunction "1_1") (pintype "power_in"))
      (node (ref "U2") (pin "2") (pinfunction "IN_2") (pintype "power_in"))
    )
    (net (code "13") (name "5V_LUP_BUS") (class "Default")
      (node (ref "R40") (pin "2") (pinfunction "2_2") (pintype "passive"))
      (node (ref "SW4") (pin "1") (pinfunction "1_1") (pintype "power_in"))
    )
    (net (code "14") (name "5V_OUT") (class "Default")
      (node (ref "C12") (pin "1") (pinfunction "1_1") (pintype "passive"))
      (node (ref "C15") (pin "2") (pinfunction "2_2") (pintype "passive"))
      (node (ref "C16") (pin "2") (pinfunction "2_2") (pintype "passive"))
      (node (ref "L2") (pin "2") (pinfunction "2_2") (pintype "passive"))
      (node (ref "R33") (pin "2") (pinfunction "2_2") (pintype "passive"))
      (node (ref "R34") (pin "1") (pinfunction "1_1") (pintype "passive"))
      (node (ref "R8") (pin "2") (pinfunction "2_2") (pintype "passive"))
      (node (ref "SW3") (pin "2") (pinfunction "2_2") (pintype "power_in"))
      (node (ref "SW4") (pin "2") (pinfunction "2_2") (pintype "power_in"))
    )
    (net (code "15") (name "8V_BUS") (class "Default")
      (node (ref "R41") (pin "2") (pinfunction "2_2") (pintype "passive"))
      (node (ref "SW5") (pin "1") (pinfunction "1_1") (pintype "power_in"))
    )
    (net (code "16") (name "8V_IN") (class "Default")
      (node (ref "C17") (pin "2") (pinfunction "2_2") (pintype "passive"))
      (node (ref "C18") (pin "2") (pinfunction "2_2") (pintype "passive"))
      (node (ref "R28") (pin "1") (pinfunction "1_1") (pintype "passive"))
      (node (ref "SW8") (pin "1") (pinfunction "1_1") (pintype "power_in"))
      (node (ref "U3") (pin "2") (pinfunction "IN_2") (pintype "power_in"))
    )
    (net (code "17") (name "8V_OUT") (class "Default")
      (node (ref "C20") (pin "1") (pinfunction "1_1") (pintype "passive"))
      (node (ref "C23") (pin "2") (pinfunction "2_2") (pintype "passive"))
      (node (ref "C24") (pin "2") (pinfunction "2_2") (pintype "passive"))
      (node (ref "L3") (pin "2") (pinfunction "2_2") (pintype "passive"))
      (node (ref "R15") (pin "2") (pinfunction "2_2") (pintype "passive"))
      (node (ref "R35") (pin "2") (pinfunction "2_2") (pintype "passive"))
      (node (ref "R36") (pin "1") (pinfunction "1_1") (pintype "passive"))
      (node (ref "SW5") (pin "2") (pinfunction "2_2") (pintype "power_in"))
    )
    (net (code "18") (name "GND") (class "Default")
      (node (ref "C1") (pin "1") (pinfunction "1_1") (pintype "passive"))
      (node (ref "C10") (pin "1") (pinfunction "1_1") (pintype "passive"))
      (node (ref "C13") (pin "1") (pinfunction "1_1") (pintype "passive"))
      (node (ref "C14") (pin "1") (pinfunction "1_1") (pintype "passive"))
      (node (ref "C15") (pin "1") (pinfunction "1_1") (pintype "passive"))
      (node (ref "C16") (pin "1") (pinfunction "1_1") (pintype "passive"))
      (node (ref "C17") (pin "1") (pinfunction "1_1") (pintype "passive"))
      (node (ref "C18") (pin "1") (pinfunction "1_1") (pintype "passive"))
      (node (ref "C2") (pin "1") (pinfunction "1_1") (pintype "passive"))
      (node (ref "C21") (pin "1") (pinfunction "1_1") (pintype "passive"))
      (node (ref "C22") (pin "1") (pinfunction "1_1") (pintype "passive"))
      (node (ref "C23") (pin "1") (pinfunction "1_1") (pintype "passive"))
      (node (ref "C24") (pin "1") (pinfunction "1_1") (pintype "passive"))
      (node (ref "C4") (pin "1") (pinfunction "1_1") (pintype "passive"))
      (node (ref "C5") (pin "1") (pinfunction "1_1") (pintype "passive"))
      (node (ref "C7") (pin "1") (pinfunction "1_1") (pintype "passive"))
      (node (ref "C8") (pin "1") (pinfunction "1_1") (pintype "passive"))
      (node (ref "C9") (pin "1") (pinfunction "1_1") (pintype "passive"))
      (node (ref "D10") (pin "C") (pinfunction "C_C") (pintype "passive"))
      (node (ref "D11") (pin "C") (pinfunction "C_C") (pintype "passive"))
      (node (ref "D4") (pin "C") (pinfunction "C_C") (pintype "passive"))
      (node (ref "D5") (pin "C") (pinfunction "C_C") (pintype "passive"))
      (node (ref "D6") (pin "C") (pinfunction "C_C") (pintype "passive"))
      (node (ref "D7") (pin "C") (pinfunction "C_C") (pintype "passive"))
      (node (ref "D8") (pin "C") (pinfunction "C_C") (pintype "passive"))
      (node (ref "D9") (pin "C") (pinfunction "C_C") (pintype "passive"))
      (node (ref "Q1") (pin "2") (pinfunction "E_2") (pintype "passive"))
      (node (ref "Q2") (pin "2") (pinfunction "E_2") (pintype "passive"))
      (node (ref "Q3") (pin "2") (pinfunction "E_2") (pintype "passive"))
      (node (ref "R17A") (pin "1") (pinfunction "1_1") (pintype "passive"))
      (node (ref "R26") (pin "1") (pinfunction "1_1") (pintype "passive"))
      (node (ref "R27") (pin "1") (pinfunction "1_1") (pintype "passive"))
      (node (ref "R6B") (pin "1") (pinfunction "1_1") (pintype "passive"))
      (node (ref "SW6") (pin "3") (pinfunction "3_3") (pintype "power_in"))
      (node (ref "SW7") (pin "3") (pinfunction "3_3") (pintype "power_in"))
      (node (ref "SW8") (pin "3") (pinfunction "3_3") (pintype "power_in"))
      (node (ref "U1") (pin "4") (pinfunction "GND_4") (pintype "passive"))
      (node (ref "U2") (pin "4") (pinfunction "GND_4") (pintype "passive"))
      (node (ref "U3") (pin "4") (pinfunction "GND_4") (pintype "passive"))
    )
    (net (code "19") (name "Net-(C3-Pad2)") (class "Default")
      (node (ref "C3") (pin "2") (pinfunction "2_2") (pintype "passive"))
      (node (ref "R1") (pin "2") (pinfunction "2_2") (pintype "passive"))
    )
    (net (code "20") (name "Net-(C6-Pad2)") (class "Default")
      (node (ref "C6") (pin "2") (pinfunction "2_2") (pintype "passive"))
      (node (ref "R22") (pin "2") (pinfunction "2_2") (pintype "passive"))
      (node (ref "R4") (pin "1") (pinfunction "1_1") (pintype "passive"))
      (node (ref "R6A") (pin "2") (pinfunction "2_2") (pintype "passive"))
    )
    (net (code "21") (name "Net-(C11-Pad2)") (class "Default")
      (node (ref "C11") (pin "2") (pinfunction "2_2") (pintype "passive"))
      (node (ref "R7") (pin "2") (pinfunction "2_2") (pintype "passive"))
    )
    (net (code "22") (name "Net-(C12-Pad2)") (class "Default")
      (node (ref "C12") (pin "2") (pinfunction "2_2") (pintype "passive"))
      (node (ref "R10") (pin "1") (pinfunction "1_1") (pintype "passive"))
      (node (ref "R11") (pin "2") (pinfunction "2_2") (pintype "passive"))
      (node (ref "R26") (pin "2") (pinfunction "2_2") (pintype "passive"))
      (node (ref "R27") (pin "2") (pinfunction "2_2") (pintype "passive"))
    )
    (net (code "23") (name "Net-(C19-Pad2)") (class "Default")
      (node (ref "C19") (pin "2") (pinfunction "2_2") (pintype "passive"))
      (node (ref "R13") (pin "2") (pinfunction "2_2") (pintype "passive"))
    )
    (net (code "24") (name "Net-(C20-Pad2)") (class "Default")
      (node (ref "C20") (pin "2") (pinfunction "2_2") (pintype "passive"))
      (node (ref "R16") (pin "1") (pinfunction "1_1") (pintype "passive"))
      (node (ref "R17A") (pin "2") (pinfunction "2_2") (pintype "passive"))
      (node (ref "R18B") (pin "2") (pinfunction "2_2") (pintype "passive"))
    )
    (net (code "25") (name "Net-(D1-PadA)") (class "Default")
      (node (ref "D1") (pin "A") (pinfunction "A_A") (pintype "passive"))
      (node (ref "R32") (pin "2") (pinfunction "2_2") (pintype "passive"))
    )
    (net (code "26") (name "Net-(D2-PadA)") (class "Default")
      (node (ref "D2") (pin "A") (pinfunction "A_A") (pintype "passive"))
      (node (ref "R34") (pin "2") (pinfunction "2_2") (pintype "passive"))
    )
    (net (code "27") (name "Net-(D3-PadA)") (class "Default")
      (node (ref "D3") (pin "A") (pinfunction "A_A") (pintype "passive"))
      (node (ref "R36") (pin "2") (pinfunction "2_2") (pintype "passive"))
    )
    (net (code "28") (name "Net-(D4-PadA)") (class "Default")
      (node (ref "D4") (pin "A") (pinfunction "A_A") (pintype "passive"))
      (node (ref "R37") (pin "1") (pinfunction "1_1") (pintype "passive"))
    )
    (net (code "29") (name "Net-(D5-PadA)") (class "Default")
      (node (ref "D5") (pin "A") (pinfunction "A_A") (pintype "passive"))
      (node (ref "R38") (pin "1") (pinfunction "1_1") (pintype "passive"))
    )
    (net (code "30") (name "Net-(D6-PadA)") (class "Default")
      (node (ref "D6") (pin "A") (pinfunction "A_A") (pintype "passive"))
      (node (ref "R39") (pin "1") (pinfunction "1_1") (pintype "passive"))
    )
    (net (code "31") (name "Net-(D7-PadA)") (class "Default")
      (node (ref "D7") (pin "A") (pinfunction "A_A") (pintype "passive"))
      (node (ref "R40") (pin "1") (pinfunction "1_1") (pintype "passive"))
    )
    (net (code "32") (name "Net-(D8-PadA)") (class "Default")
      (node (ref "D8") (pin "A") (pinfunction "A_A") (pintype "passive"))
      (node (ref "R41") (pin "1") (pinfunction "1_1") (pintype "passive"))
    )
    (net (code "33") (name "Net-(D9-PadA)") (class "Default")
      (node (ref "D9") (pin "A") (pinfunction "A_A") (pintype "passive"))
      (node (ref "R43") (pin "2") (pinfunction "2_2") (pintype "passive"))
    )
    (net (code "34") (name "Net-(D10-PadA)") (class "Default")
      (node (ref "D10") (pin "A") (pinfunction "A_A") (pintype "passive"))
      (node (ref "R45") (pin "2") (pinfunction "2_2") (pintype "passive"))
    )
    (net (code "35") (name "Net-(D11-PadA)") (class "Default")
      (node (ref "D11") (pin "A") (pinfunction "A_A") (pintype "passive"))
      (node (ref "R47") (pin "2") (pinfunction "2_2") (pintype "passive"))
    )
    (net (code "36") (name "Net-(Q1-C)") (class "Default")
      (node (ref "D1") (pin "C") (pinfunction "C_C") (pintype "passive"))
      (node (ref "Q1") (pin "3") (pinfunction "C_3") (pintype "passive"))
    )
    (net (code "37") (name "Net-(Q2-C)") (class "Default")
      (node (ref "D2") (pin "C") (pinfunction "C_C") (pintype "passive"))
      (node (ref "Q2") (pin "3") (pinfunction "C_3") (pintype "passive"))
    )
    (net (code "38") (name "Net-(Q3-C)") (class "Default")
      (node (ref "D3") (pin "C") (pinfunction "C_C") (pintype "passive"))
      (node (ref "Q3") (pin "3") (pinfunction "C_3") (pintype "passive"))
    )
    (net (code "39") (name "Net-(R2-Pad1)") (class "Default")
      (node (ref "R2") (pin "1") (pinfunction "1_1") (pintype "passive"))
      (node (ref "R3") (pin "2") (pinfunction "2_2") (pintype "passive"))
    )
    (net (code "40") (name "Net-(R3-Pad1)") (class "Default")
      (node (ref "R3") (pin "1") (pinfunction "1_1") (pintype "passive"))
      (node (ref "R4") (pin "2") (pinfunction "2_2") (pintype "passive"))
    )
    (net (code "41") (name "Net-(R6A-Pad1)") (class "Default")
      (node (ref "R6A") (pin "1") (pinfunction "1_1") (pintype "passive"))
      (node (ref "R6B") (pin "2") (pinfunction "2_2") (pintype "passive"))
    )
    (net (code "42") (name "Net-(R8-Pad1)") (class "Default")
      (node (ref "R8") (pin "1") (pinfunction "1_1") (pintype "passive"))
      (node (ref "R9") (pin "2") (pinfunction "2_2") (pintype "passive"))
    )
    (net (code "43") (name "Net-(R10-Pad2)") (class "Default")
      (node (ref "R10") (pin "2") (pinfunction "2_2") (pintype "passive"))
      (node (ref "R9") (pin "1") (pinfunction "1_1") (pintype "passive"))
    )
    (net (code "44") (name "Net-(R15-Pad1)") (class "Default")
      (node (ref "R15") (pin "1") (pinfunction "1_1") (pintype "passive"))
      (node (ref "R16") (pin "2") (pinfunction "2_2") (pintype "passive"))
    )
    (net (code "45") (name "Net-(R18A-Pad2)") (class "Default")
      (node (ref "R18A") (pin "2") (pinfunction "2_2") (pintype "passive"))
      (node (ref "R18B") (pin "1") (pinfunction "1_1") (pintype "passive"))
    )
    (net (code "46") (name "Net-(R19-Pad1)") (class "Default")
      (node (ref "R19") (pin "1") (pinfunction "1_1") (pintype "passive"))
      (node (ref "R20") (pin "1") (pinfunction "1_1") (pintype "passive"))
    )
    (net (code "47") (name "Net-(R20-Pad2)") (class "Default")
      (node (ref "R20") (pin "2") (pinfunction "2_2") (pintype "passive"))
      (node (ref "R21") (pin "2") (pinfunction "2_2") (pintype "passive"))
    )
    (net (code "48") (name "Net-(R22-Pad1)") (class "Default")
      (node (ref "R22") (pin "1") (pinfunction "1_1") (pintype "passive"))
      (node (ref "R5") (pin "2") (pinfunction "2_2") (pintype "passive"))
    )
    (net (code "49") (name "Net-(R23-Pad1)") (class "Default")
      (node (ref "R23") (pin "1") (pinfunction "1_1") (pintype "passive"))
      (node (ref "R24") (pin "1") (pinfunction "1_1") (pintype "passive"))
    )
    (net (code "50") (name "Net-(R24-Pad2)") (class "Default")
      (node (ref "R24") (pin "2") (pinfunction "2_2") (pintype "passive"))
      (node (ref "R25") (pin "2") (pinfunction "2_2") (pintype "passive"))
    )
    (net (code "51") (name "Net-(R28-Pad2)") (class "Default")
      (node (ref "R28") (pin "2") (pinfunction "2_2") (pintype "passive"))
      (node (ref "R29") (pin "1") (pinfunction "1_1") (pintype "passive"))
    )
    (net (code "52") (name "Net-(R29-Pad2)") (class "Default")
      (node (ref "R29") (pin "2") (pinfunction "2_2") (pintype "passive"))
      (node (ref "R30") (pin "2") (pinfunction "2_2") (pintype "passive"))
    )
    (net (code "53") (name "Net-(R42-Pad1)") (class "Default")
      (node (ref "R42") (pin "1") (pinfunction "1_1") (pintype "passive"))
      (node (ref "R43") (pin "1") (pinfunction "1_1") (pintype "passive"))
      (node (ref "SW6") (pin "2") (pinfunction "2_2") (pintype "power_in"))
    )
    (net (code "54") (name "Net-(R44-Pad1)") (class "Default")
      (node (ref "R44") (pin "1") (pinfunction "1_1") (pintype "passive"))
      (node (ref "R45") (pin "1") (pinfunction "1_1") (pintype "passive"))
      (node (ref "SW7") (pin "2") (pinfunction "2_2") (pintype "power_in"))
    )
    (net (code "55") (name "Net-(R46-Pad1)") (class "Default")
      (node (ref "R46") (pin "1") (pinfunction "1_1") (pintype "passive"))
      (node (ref "R47") (pin "1") (pinfunction "1_1") (pintype "passive"))
      (node (ref "SW8") (pin "2") (pinfunction "2_2") (pintype "power_in"))
    )
    (net (code "56") (name "Net-(U1-BST)") (class "Default")
      (node (ref "R1") (pin "1") (pinfunction "1_1") (pintype "passive"))
      (node (ref "U1") (pin "5") (pinfunction "BST_5") (pintype "power_in"))
    )
    (net (code "57") (name "Net-(U1-FB)") (class "Default")
      (node (ref "R5") (pin "1") (pinfunction "1_1") (pintype "passive"))
      (node (ref "U1") (pin "8") (pinfunction "FB_8") (pintype "power_in"))
    )
    (net (code "58") (name "Net-(U1-SS)") (class "Default")
      (node (ref "C8") (pin "2") (pinfunction "2_2") (pintype "passive"))
      (node (ref "U1") (pin "7") (pinfunction "SS_7") (pintype "passive"))
    )
    (net (code "59") (name "Net-(U1-SW)") (class "Default")
      (node (ref "C3") (pin "1") (pinfunction "1_1") (pintype "passive"))
      (node (ref "L1") (pin "1") (pinfunction "1_1") (pintype "passive"))
      (node (ref "U1") (pin "3") (pinfunction "SW_3") (pintype "passive"))
    )
    (net (code "60") (name "Net-(U2-BST)") (class "Default")
      (node (ref "R7") (pin "1") (pinfunction "1_1") (pintype "passive"))
      (node (ref "U2") (pin "5") (pinfunction "BST_5") (pintype "power_in"))
    )
    (net (code "61") (name "Net-(U2-FB)") (class "Default")
      (node (ref "R11") (pin "1") (pinfunction "1_1") (pintype "passive"))
      (node (ref "U2") (pin "8") (pinfunction "FB_8") (pintype "power_in"))
    )
    (net (code "62") (name "Net-(U2-SS)") (class "Default")
      (node (ref "C13") (pin "2") (pinfunction "2_2") (pintype "passive"))
      (node (ref "U2") (pin "7") (pinfunction "SS_7") (pintype "passive"))
    )
    (net (code "63") (name "Net-(U2-SW)") (class "Default")
      (node (ref "C11") (pin "1") (pinfunction "1_1") (pintype "passive"))
      (node (ref "L2") (pin "1") (pinfunction "1_1") (pintype "passive"))
      (node (ref "U2") (pin "3") (pinfunction "SW_3") (pintype "passive"))
    )
    (net (code "64") (name "Net-(U3-BST)") (class "Default")
      (node (ref "R13") (pin "1") (pinfunction "1_1") (pintype "passive"))
      (node (ref "U3") (pin "5") (pinfunction "BST_5") (pintype "power_in"))
    )
    (net (code "65") (name "Net-(U3-FB)") (class "Default")
      (node (ref "R18A") (pin "1") (pinfunction "1_1") (pintype "passive"))
      (node (ref "U3") (pin "8") (pinfunction "FB_8") (pintype "power_in"))
    )
    (net (code "66") (name "Net-(U3-SS)") (class "Default")
      (node (ref "C21") (pin "2") (pinfunction "2_2") (pintype "passive"))
      (node (ref "U3") (pin "7") (pinfunction "SS_7") (pintype "passive"))
    )
    (net (code "67") (name "Net-(U3-SW)") (class "Default")
      (node (ref "C19") (pin "1") (pinfunction "1_1") (pintype "passive"))
      (node (ref "L3") (pin "1") (pinfunction "1_1") (pintype "passive"))
      (node (ref "U3") (pin "3") (pinfunction "SW_3") (pintype "passive"))
    )
    (net (code "68") (name "unconnected-(SW1-Pad3)") (class "Default")
      (node (ref "SW1") (pin "3") (pinfunction "3_3") (pintype "power_in+no_connect"))
    )
    (net (code "69") (name "unconnected-(SW2-Pad3)") (class "Default")
      (node (ref "SW2") (pin "3") (pinfunction "3_3") (pintype "power_in+no_connect"))
    )
    (net (code "70") (name "unconnected-(SW3-Pad3)") (class "Default")
      (node (ref "SW3") (pin "3") (pinfunction "3_3") (pintype "power_in+no_connect"))
    )
    (net (code "71") (name "unconnected-(SW4-Pad3)") (class "Default")
      (node (ref "SW4") (pin "3") (pinfunction "3_3") (pintype "power_in+no_connect"))
    )
    (net (code "72") (name "unconnected-(SW5-Pad3)") (class "Default")
      (node (ref "SW5") (pin "3") (pinfunction "3_3") (pintype "power_in+no_connect"))
    )
  )
)
